# driver2.net
KiCad netlist of a schematic drawn in EAGLE
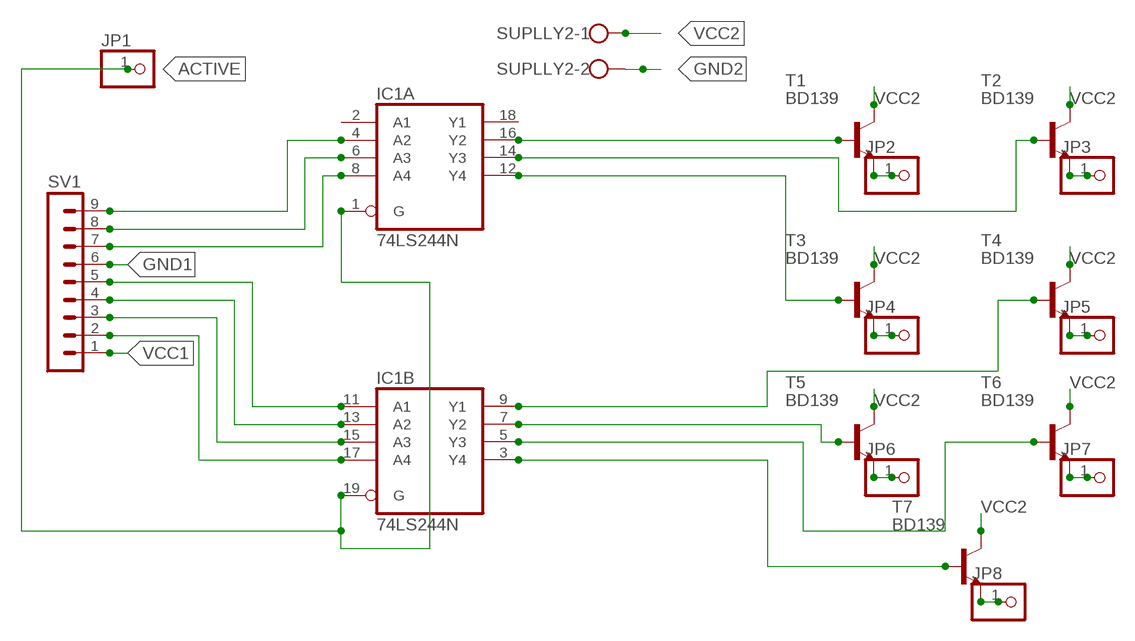
[diagram p0: schematic, sheet 1]

(export (version "E")
  (design (tool "Eeschema 10.0.6"))
  (components
    (comp (ref "IC1")
      (value "74LS244N")
      (footprint "eagle-import:DIL20")
      (libsource (lib "eagle-import") (part "74244NLS"))
    )
    (comp (ref "JP1")
      (value "PINHD-1X1")
      (footprint "eagle-import:1X01")
      (libsource (lib "eagle-import") (part "PINHD-1X1"))
    )
    (comp (ref "JP2")
      (value "PINHD-1X1")
      (footprint "eagle-import:1X01")
      (libsource (lib "eagle-import") (part "PINHD-1X1"))
    )
    (comp (ref "JP3")
      (value "PINHD-1X1")
      (footprint "eagle-import:1X01")
      (libsource (lib "eagle-import") (part "PINHD-1X1"))
    )
    (comp (ref "JP4")
      (value "PINHD-1X1")
      (footprint "eagle-import:1X01")
      (libsource (lib "eagle-import") (part "PINHD-1X1"))
    )
    (comp (ref "JP5")
      (value "PINHD-1X1")
      (footprint "eagle-import:1X01")
      (libsource (lib "eagle-import") (part "PINHD-1X1"))
    )
    (comp (ref "JP6")
      (value "PINHD-1X1")
      (footprint "eagle-import:1X01")
      (libsource (lib "eagle-import") (part "PINHD-1X1"))
    )
    (comp (ref "JP7")
      (value "PINHD-1X1")
      (footprint "eagle-import:1X01")
      (libsource (lib "eagle-import") (part "PINHD-1X1"))
    )
    (comp (ref "JP8")
      (value "PINHD-1X1")
      (footprint "eagle-import:1X01")
      (libsource (lib "eagle-import") (part "PINHD-1X1"))
    )
    (comp (ref "SUPLLY2")
      (value "W237-102")
      (footprint "eagle-import:W237-102")
      (fields (field (name "MPN") "237-102"))
      (libsource (lib "eagle-import") (part "W237-102"))
    )
    (comp (ref "SV1")
      (value "MA09-1")
      (footprint "eagle-import:MA09-1")
      (libsource (lib "eagle-import") (part "MA09-1"))
    )
    (comp (ref "T1")
      (value "BD139")
      (footprint "eagle-import:TO126")
      (libsource (lib "eagle-import") (part "BD139"))
    )
    (comp (ref "T2")
      (value "BD139")
      (footprint "eagle-import:TO126")
      (libsource (lib "eagle-import") (part "BD139"))
    )
    (comp (ref "T3")
      (value "BD139")
      (footprint "eagle-import:TO126")
      (libsource (lib "eagle-import") (part "BD139"))
    )
    (comp (ref "T4")
      (value "BD139")
      (footprint "eagle-import:TO126")
      (libsource (lib "eagle-import") (part "BD139"))
    )
    (comp (ref "T5")
      (value "BD139")
      (footprint "eagle-import:TO126")
      (libsource (lib "eagle-import") (part "BD139"))
    )
    (comp (ref "T6")
      (value "BD139")
      (footprint "eagle-import:TO126")
      (libsource (lib "eagle-import") (part "BD139"))
    )
    (comp (ref "T7")
      (value "BD139")
      (footprint "eagle-import:TO126")
      (libsource (lib "eagle-import") (part "BD139"))
    )
  )
  (nets
    (net (code "1") (name "ACTIVE") (class "Default")
      (node (ref "IC1") (pin "1") (pinfunction "G_1") (pintype "input"))
      (node (ref "IC1") (pin "19") (pinfunction "G_19") (pintype "input"))
      (node (ref "JP1") (pin "1") (pinfunction "1_1") (pintype "passive"))
    )
    (net (code "2") (name "GND1") (class "Default")
      (node (ref "SV1") (pin "6") (pinfunction "6_6") (pintype "passive"))
    )
    (net (code "3") (name "GND2") (class "Default")
      (node (ref "SUPLLY2") (pin "2") (pinfunction "KL_2") (pintype "passive"))
    )
    (net (code "4") (name "Net-(IC1A-A2)") (class "Default")
      (node (ref "IC1") (pin "4") (pinfunction "A2_4") (pintype "input"))
      (node (ref "SV1") (pin "9") (pinfunction "9_9") (pintype "passive"))
    )
    (net (code "5") (name "Net-(IC1A-A3)") (class "Default")
      (node (ref "IC1") (pin "6") (pinfunction "A3_6") (pintype "input"))
      (node (ref "SV1") (pin "8") (pinfunction "8_8") (pintype "passive"))
    )
    (net (code "6") (name "Net-(IC1A-A4)") (class "Default")
      (node (ref "IC1") (pin "8") (pinfunction "A4_8") (pintype "input"))
      (node (ref "SV1") (pin "7") (pinfunction "7_7") (pintype "passive"))
    )
    (net (code "7") (name "Net-(IC1A-Y2)") (class "Default")
      (node (ref "IC1") (pin "16") (pinfunction "Y2_16") (pintype "tri_state"))
      (node (ref "T1") (pin "3") (pinfunction "B_3") (pintype "passive"))
    )
    (net (code "8") (name "Net-(IC1A-Y3)") (class "Default")
      (node (ref "IC1") (pin "14") (pinfunction "Y3_14") (pintype "tri_state"))
      (node (ref "T2") (pin "3") (pinfunction "B_3") (pintype "passive"))
    )
    (net (code "9") (name "Net-(IC1A-Y4)") (class "Default")
      (node (ref "IC1") (pin "12") (pinfunction "Y4_12") (pintype "tri_state"))
      (node (ref "T3") (pin "3") (pinfunction "B_3") (pintype "passive"))
    )
    (net (code "10") (name "Net-(IC1B-A1)") (class "Default")
      (node (ref "IC1") (pin "11") (pinfunction "A1_11") (pintype "input"))
      (node (ref "SV1") (pin "5") (pinfunction "5_5") (pintype "passive"))
    )
    (net (code "11") (name "Net-(IC1B-A2)") (class "Default")
      (node (ref "IC1") (pin "13") (pinfunction "A2_13") (pintype "input"))
      (node (ref "SV1") (pin "4") (pinfunction "4_4") (pintype "passive"))
    )
    (net (code "12") (name "Net-(IC1B-A3)") (class "Default")
      (node (ref "IC1") (pin "15") (pinfunction "A3_15") (pintype "input"))
      (node (ref "SV1") (pin "3") (pinfunction "3_3") (pintype "passive"))
    )
    (net (code "13") (name "Net-(IC1B-A4)") (class "Default")
      (node (ref "IC1") (pin "17") (pinfunction "A4_17") (pintype "input"))
      (node (ref "SV1") (pin "2") (pinfunction "2_2") (pintype "passive"))
    )
    (net (code "14") (name "Net-(IC1B-Y1)") (class "Default")
      (node (ref "IC1") (pin "9") (pinfunction "Y1_9") (pintype "tri_state"))
      (node (ref "T4") (pin "3") (pinfunction "B_3") (pintype "passive"))
    )
    (net (code "15") (name "Net-(IC1B-Y2)") (class "Default")
      (node (ref "IC1") (pin "7") (pinfunction "Y2_7") (pintype "tri_state"))
      (node (ref "T5") (pin "3") (pinfunction "B_3") (pintype "passive"))
    )
    (net (code "16") (name "Net-(IC1B-Y3)") (class "Default")
      (node (ref "IC1") (pin "5") (pinfunction "Y3_5") (pintype "tri_state"))
      (node (ref "T6") (pin "3") (pinfunction "B_3") (pintype "passive"))
    )
    (net (code "17") (name "Net-(IC1B-Y4)") (class "Default")
      (node (ref "IC1") (pin "3") (pinfunction "Y4_3") (pintype "tri_state"))
      (node (ref "T7") (pin "3") (pinfunction "B_3") (pintype "passive"))
    )
    (net (code "18") (name "Net-(T1-E)") (class "Default")
      (node (ref "JP2") (pin "1") (pinfunction "1_1") (pintype "passive"))
      (node (ref "T1") (pin "1") (pinfunction "E_1") (pintype "passive"))
    )
    (net (code "19") (name "Net-(T2-E)") (class "Default")
      (node (ref "JP3") (pin "1") (pinfunction "1_1") (pintype "passive"))
      (node (ref "T2") (pin "1") (pinfunction "E_1") (pintype "passive"))
    )
    (net (code "20") (name "Net-(T3-E)") (class "Default")
      (node (ref "JP4") (pin "1") (pinfunction "1_1") (pintype "passive"))
      (node (ref "T3") (pin "1") (pinfunction "E_1") (pintype "passive"))
    )
    (net (code "21") (name "Net-(T4-E)") (class "Default")
      (node (ref "JP5") (pin "1") (pinfunction "1_1") (pintype "passive"))
      (node (ref "T4") (pin "1") (pinfunction "E_1") (pintype "passive"))
    )
    (net (code "22") (name "Net-(T5-E)") (class "Default")
      (node (ref "JP6") (pin "1") (pinfunction "1_1") (pintype "passive"))
      (node (ref "T5") (pin "1") (pinfunction "E_1") (pintype "passive"))
    )
    (net (code "23") (name "Net-(T6-E)") (class "Default")
      (node (ref "JP7") (pin "1") (pinfunction "1_1") (pintype "passive"))
      (node (ref "T6") (pin "1") (pinfunction "E_1") (pintype "passive"))
    )
    (net (code "24") (name "Net-(T7-E)") (class "Default")
      (node (ref "JP8") (pin "1") (pinfunction "1_1") (pintype "passive"))
      (node (ref "T7") (pin "1") (pinfunction "E_1") (pintype "passive"))
    )
    (net (code "25") (name "VCC1") (class "Default")
      (node (ref "SV1") (pin "1") (pinfunction "1_1") (pintype "passive"))
    )
    (net (code "26") (name "VCC2") (class "Default")
      (node (ref "SUPLLY2") (pin "1") (pinfunction "KL_1") (pintype "passive"))
      (node (ref "T1") (pin "2") (pinfunction "C_2") (pintype "passive"))
      (node (ref "T2") (pin "2") (pinfunction "C_2") (pintype "passive"))
      (node (ref "T3") (pin "2") (pinfunction "C_2") (pintype "passive"))
      (node (ref "T4") (pin "2") (pinfunction "C_2") (pintype "passive"))
      (node (ref "T5") (pin "2") (pinfunction "C_2") (pintype "passive"))
      (node (ref "T6") (pin "2") (pinfunction "C_2") (pintype "passive"))
      (node (ref "T7") (pin "2") (pinfunction "C_2") (pintype "passive"))
    )
    (net (code "27") (name "unconnected-(IC1A-A1-Pad2)") (class "Default")
      (node (ref "IC1") (pin "2") (pinfunction "A1_2") (pintype "input"))
    )
    (net (code "28") (name "unconnected-(IC1A-Y1-Pad18)") (class "Default")
      (node (ref "IC1") (pin "18") (pinfunction "Y1_18") (pintype "tri_state"))
    )
  )
)
